# SW6106_A_C_LED.net
KiCad netlist of a schematic drawn in Altium Designer
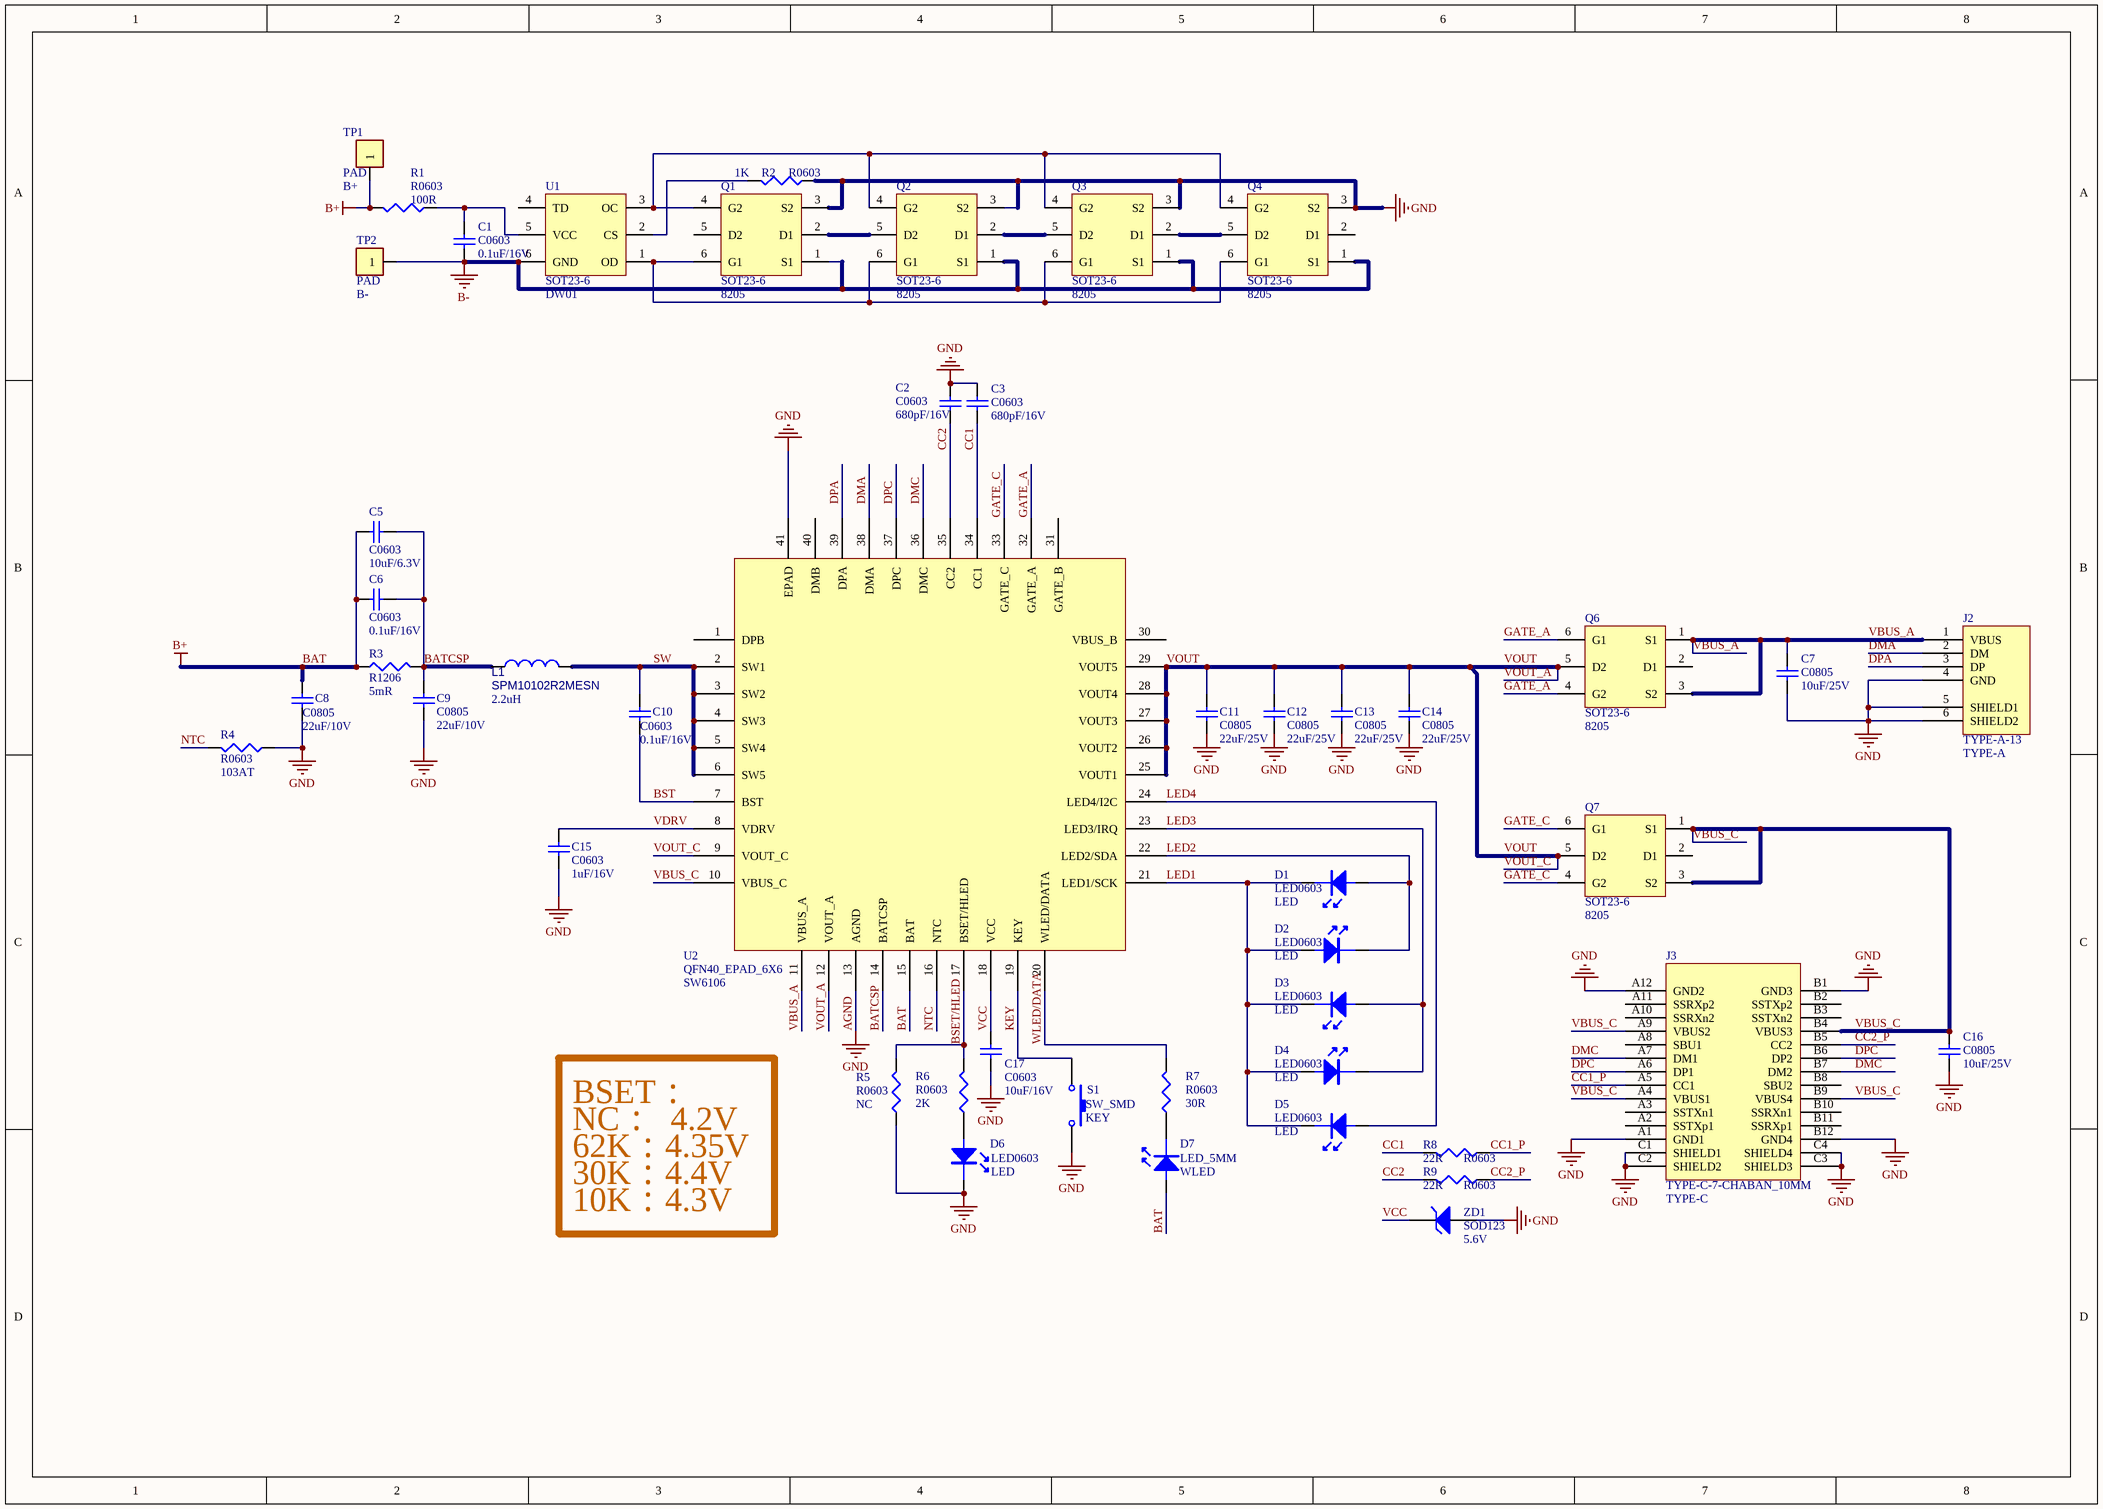
[diagram p0: SW6106+A+C+LED.SchDoc]

(export (version "E")
  (design (tool "Eeschema 10.0.6"))
  (components
    (comp (ref "C1")
      (value "C0603")
      (footprint "C0603")
      (description "Capacitor")
      (fields (field (name "ALTIUM_VALUE") "0.1uF/16V") (field (name "PUBLISHER") "Altium Limited"))
      (libsource (lib "*") (part "Cap"))
    )
    (comp (ref "C2")
      (value "C0603")
      (footprint "C0603")
      (description "Capacitor")
      (fields (field (name "ALTIUM_VALUE") "680pF/16V") (field (name "PUBLISHER") "Altium Limited"))
      (libsource (lib "*") (part "CAP0603"))
    )
    (comp (ref "C3")
      (value "C0603")
      (footprint "C0603")
      (description "Capacitor")
      (fields (field (name "ALTIUM_VALUE") "680pF/16V") (field (name "PUBLISHER") "Altium Limited"))
      (libsource (lib "*") (part "CAP0603"))
    )
    (comp (ref "C5")
      (value "C0603")
      (footprint "C0603")
      (description "Capacitor")
      (fields (field (name "ALTIUM_VALUE") "10uF/6.3V") (field (name "PUBLISHER") "Altium Limited"))
      (libsource (lib "*") (part "CAP0603"))
    )
    (comp (ref "C6")
      (value "C0603")
      (footprint "C0603")
      (description "Capacitor")
      (fields (field (name "ALTIUM_VALUE") "0.1uF/16V") (field (name "PUBLISHER") "Altium Limited"))
      (libsource (lib "*") (part "CAP0603"))
    )
    (comp (ref "C7")
      (value "C0805")
      (footprint "C0805")
      (description "Capacitor")
      (fields (field (name "ALTIUM_VALUE") "10uF/25V") (field (name "PUBLISHER") "Altium Limited"))
      (libsource (lib "*") (part "CAP0603"))
    )
    (comp (ref "C8")
      (value "C0805")
      (footprint "C0805")
      (description "Capacitor")
      (fields (field (name "ALTIUM_VALUE") "22uF/10V") (field (name "PUBLISHER") "Altium Limited"))
      (libsource (lib "*") (part "CAP0805"))
    )
    (comp (ref "C9")
      (value "C0805")
      (footprint "C0805")
      (description "Capacitor")
      (fields (field (name "ALTIUM_VALUE") "22uF/10V") (field (name "PUBLISHER") "Altium Limited"))
      (libsource (lib "*") (part "CAP0805"))
    )
    (comp (ref "C10")
      (value "C0603")
      (footprint "C0603")
      (description "Capacitor")
      (fields (field (name "ALTIUM_VALUE") "0.1uF/16V") (field (name "PUBLISHER") "Altium Limited"))
      (libsource (lib "*") (part "CAP0603"))
    )
    (comp (ref "C11")
      (value "C0805")
      (footprint "C0805")
      (description "Capacitor")
      (fields (field (name "ALTIUM_VALUE") "22uF/25V") (field (name "PUBLISHER") "Altium Limited"))
      (libsource (lib "*") (part "CAP0805"))
    )
    (comp (ref "C12")
      (value "C0805")
      (footprint "C0805")
      (description "Capacitor")
      (fields (field (name "ALTIUM_VALUE") "22uF/25V") (field (name "PUBLISHER") "Altium Limited"))
      (libsource (lib "*") (part "CAP0805"))
    )
    (comp (ref "C13")
      (value "C0805")
      (footprint "C0805")
      (description "Capacitor")
      (fields (field (name "ALTIUM_VALUE") "22uF/25V") (field (name "PUBLISHER") "Altium Limited"))
      (libsource (lib "*") (part "CAP0805"))
    )
    (comp (ref "C14")
      (value "C0805")
      (footprint "C0805")
      (description "Capacitor")
      (fields (field (name "ALTIUM_VALUE") "22uF/25V") (field (name "PUBLISHER") "Altium Limited"))
      (libsource (lib "*") (part "CAP0805"))
    )
    (comp (ref "C15")
      (value "C0603")
      (footprint "C0603")
      (description "Capacitor")
      (fields (field (name "ALTIUM_VALUE") "1uF/16V") (field (name "PUBLISHER") "Altium Limited"))
      (libsource (lib "*") (part "CAP0603"))
    )
    (comp (ref "C16")
      (value "C0805")
      (footprint "C0805")
      (description "Capacitor")
      (fields (field (name "ALTIUM_VALUE") "10uF/25V") (field (name "PUBLISHER") "Altium Limited"))
      (libsource (lib "*") (part "CAP0603"))
    )
    (comp (ref "C17")
      (value "C0603")
      (footprint "C0603")
      (description "Capacitor")
      (fields (field (name "ALTIUM_VALUE") "10uF/16V") (field (name "PUBLISHER") "Altium Limited"))
      (libsource (lib "*") (part "CAP0603"))
    )
    (comp (ref "D1") (value "LED") (footprint "LED0603") (libsource (lib "*") (part "LED")))
    (comp (ref "D2") (value "LED") (footprint "LED0603") (libsource (lib "*") (part "LED")))
    (comp (ref "D3") (value "LED") (footprint "LED0603") (libsource (lib "*") (part "LED")))
    (comp (ref "D4") (value "LED") (footprint "LED0603") (libsource (lib "*") (part "LED")))
    (comp (ref "D5") (value "LED") (footprint "LED0603") (libsource (lib "*") (part "LED")))
    (comp (ref "D6") (value "LED") (footprint "LED0603") (libsource (lib "*") (part "LED")))
    (comp (ref "D7")
      (value "WLED")
      (footprint "LED_5MM")
      (fields (field (name "FOOTPRINF") "LED_5MM") (field (name "Comment") "LED_5MM"))
      (libsource (lib "*") (part "LED"))
    )
    (comp (ref "J2")
      (value "TYPE-A")
      (footprint "TYPE-A-13")
      (fields (field (name "FOOTPRINF") "TYPE-A-13") (field (name "Comment") "TYPE-A-1"))
      (libsource (lib "*") (part "TYPE-A-1"))
    )
    (comp (ref "J3")
      (value "TYPE-C")
      (footprint "TYPE-C-7-CHABAN_10MM")
      (libsource (lib "*") (part "TYPE-C"))
    )
    (comp (ref "L1")
      (value "SPM10102R2MESN")
      (footprint "INDUCTOR_SPM1010")
      (fields (field (name "ALTIUM_VALUE") "2.2uH"))
      (libsource (lib "*") (part "INDUCTOR"))
    )
    (comp (ref "Q1")
      (value "8205")
      (footprint "SOT23-6")
      (fields (field (name "FOOTPRINF") "SOT23-6"))
      (libsource (lib "") (part "8205B_1"))
    )
    (comp (ref "Q2")
      (value "8205")
      (footprint "SOT23-6")
      (fields (field (name "FOOTPRINF") "SOT23-6"))
      (libsource (lib "") (part "8205B_1"))
    )
    (comp (ref "Q3")
      (value "8205")
      (footprint "SOT23-6")
      (fields (field (name "FOOTPRINF") "SOT23-6"))
      (libsource (lib "") (part "8205B_1"))
    )
    (comp (ref "Q4")
      (value "8205")
      (footprint "SOT23-6")
      (fields (field (name "FOOTPRINF") "SOT23-6"))
      (libsource (lib "") (part "8205B_1"))
    )
    (comp (ref "Q6")
      (value "8205")
      (footprint "SOT23-6")
      (fields (field (name "FOOTPRINF") "SOT23-6"))
      (libsource (lib "*") (part "8205B"))
    )
    (comp (ref "Q7")
      (value "8205")
      (footprint "SOT23-6")
      (fields (field (name "FOOTPRINF") "SOT23-6"))
      (libsource (lib "*") (part "8205B"))
    )
    (comp (ref "R1")
      (value "R0603")
      (footprint "R0603")
      (description "Resistor")
      (fields (field (name "ALTIUM_VALUE") "100R") (field (name "PUBLISHER") "Altium Limited"))
      (libsource (lib "*") (part "Res3"))
    )
    (comp (ref "R2")
      (value "R0603")
      (footprint "R0603")
      (description "Resistor")
      (fields (field (name "ALTIUM_VALUE") "1K") (field (name "PUBLISHER") "Altium Limited"))
      (libsource (lib "*") (part "Res3"))
    )
    (comp (ref "R3")
      (value "R1206")
      (footprint "R1206")
      (description "Resistor")
      (fields (field (name "ALTIUM_VALUE") "5mR") (field (name "PUBLISHER") "Altium Limited"))
      (libsource (lib "*") (part "RES"))
    )
    (comp (ref "R4")
      (value "R0603")
      (footprint "R0603")
      (description "Resistor")
      (fields (field (name "ALTIUM_VALUE") "103AT") (field (name "PUBLISHER") "Altium Limited"))
      (libsource (lib "*") (part "RES"))
    )
    (comp (ref "R5")
      (value "R0603")
      (footprint "R0603")
      (description "Resistor")
      (fields (field (name "ALTIUM_VALUE") "NC") (field (name "PUBLISHER") "Altium Limited"))
      (libsource (lib "*") (part "RES"))
    )
    (comp (ref "R6")
      (value "R0603")
      (footprint "R0603")
      (description "Resistor")
      (fields (field (name "ALTIUM_VALUE") "2K") (field (name "PUBLISHER") "Altium Limited"))
      (libsource (lib "*") (part "RES"))
    )
    (comp (ref "R7")
      (value "R0603")
      (footprint "R0603")
      (description "Resistor")
      (fields (field (name "ALTIUM_VALUE") "30R") (field (name "PUBLISHER") "Altium Limited"))
      (libsource (lib "*") (part "RES"))
    )
    (comp (ref "R8")
      (value "R0603")
      (footprint "R0603")
      (description "Resistor")
      (fields (field (name "ALTIUM_VALUE") "22R") (field (name "PUBLISHER") "Altium Limited"))
      (libsource (lib "*") (part "RES"))
    )
    (comp (ref "R9")
      (value "R0603")
      (footprint "R0603")
      (description "Resistor")
      (fields (field (name "ALTIUM_VALUE") "22R") (field (name "PUBLISHER") "Altium Limited"))
      (libsource (lib "*") (part "RES"))
    )
    (comp (ref "S1")
      (value "KEY")
      (footprint "SW_SMD")
      (fields (field (name "FOOTPRINF") "SW_SMD"))
      (libsource (lib "*") (part "SW K"))
    )
    (comp (ref "TP1") (value "B+") (footprint "PAD") (libsource (lib "") (part "Test Point_1")))
    (comp (ref "TP2") (value "B-") (footprint "PAD") (libsource (lib "*") (part "Test Point")))
    (comp (ref "U1")
      (value "DW01")
      (footprint "SOT23-6")
      (fields (field (name "FOOTPRINF") "SOT23-6"))
      (libsource (lib "*") (part "DW01"))
    )
    (comp (ref "U2")
      (value "SW6106")
      (footprint "QFN40_EPAD_6X6")
      (libsource (lib "TEST") (part "SW6106_AFC"))
    )
    (comp (ref "ZD1")
      (value "SOD123")
      (footprint "SOD-123")
      (description "Zener Diode")
      (fields (field (name "ALTIUM_UNNAMED_1") "5.6V"))
      (libsource (lib "Miscellaneous Devices") (part "D Zener"))
    )
  )
  (nets
    (net (code "1") (name "/BATCSP") (class "Default")
      (node (ref "C5") (pin "2") (pinfunction "2_2") (pintype "passive"))
      (node (ref "C6") (pin "2") (pinfunction "2_2") (pintype "passive"))
      (node (ref "C9") (pin "2") (pinfunction "2_2") (pintype "passive"))
      (node (ref "L1") (pin "1") (pinfunction "1_1") (pintype "passive"))
      (node (ref "R3") (pin "2") (pinfunction "2_2") (pintype "passive"))
      (node (ref "U2") (pin "14") (pinfunction "BATCSP_14") (pintype "passive"))
    )
    (net (code "2") (name "/BSET{slash}HLED") (class "Default")
      (node (ref "R5") (pin "2") (pinfunction "2_2") (pintype "passive"))
      (node (ref "R6") (pin "2") (pinfunction "2_2") (pintype "passive"))
      (node (ref "U2") (pin "17") (pinfunction "BSET/HLED_17") (pintype "passive"))
    )
    (net (code "3") (name "/BST") (class "Default")
      (node (ref "C10") (pin "1") (pinfunction "1_1") (pintype "passive"))
      (node (ref "U2") (pin "7") (pinfunction "BST_7") (pintype "passive"))
    )
    (net (code "4") (name "/CC1") (class "Default")
      (node (ref "C3") (pin "1") (pinfunction "1_1") (pintype "passive"))
      (node (ref "R8") (pin "2") (pinfunction "2_2") (pintype "passive"))
      (node (ref "U2") (pin "34") (pinfunction "CC1_34") (pintype "passive"))
    )
    (net (code "5") (name "/CC1_P") (class "Default")
      (node (ref "J3") (pin "A5") (pinfunction "CC1_A5") (pintype "passive"))
      (node (ref "R8") (pin "1") (pinfunction "1_1") (pintype "passive"))
    )
    (net (code "6") (name "/CC2") (class "Default")
      (node (ref "C2") (pin "1") (pinfunction "1_1") (pintype "passive"))
      (node (ref "R9") (pin "2") (pinfunction "2_2") (pintype "passive"))
      (node (ref "U2") (pin "35") (pinfunction "CC2_35") (pintype "passive"))
    )
    (net (code "7") (name "/CC2_P") (class "Default")
      (node (ref "J3") (pin "B5") (pinfunction "CC2_B5") (pintype "passive"))
      (node (ref "R9") (pin "1") (pinfunction "1_1") (pintype "passive"))
    )
    (net (code "8") (name "/DMA") (class "Default")
      (node (ref "J2") (pin "2") (pinfunction "DM_2") (pintype "passive"))
      (node (ref "U2") (pin "38") (pinfunction "DMA_38") (pintype "passive"))
    )
    (net (code "9") (name "/DMC") (class "Default")
      (node (ref "J3") (pin "A7") (pinfunction "DM1_A7") (pintype "passive"))
      (node (ref "J3") (pin "B7") (pinfunction "DM2_B7") (pintype "passive"))
      (node (ref "U2") (pin "36") (pinfunction "DMC_36") (pintype "passive"))
    )
    (net (code "10") (name "/DPA") (class "Default")
      (node (ref "J2") (pin "3") (pinfunction "DP_3") (pintype "passive"))
      (node (ref "U2") (pin "39") (pinfunction "DPA_39") (pintype "passive"))
    )
    (net (code "11") (name "/DPC") (class "Default")
      (node (ref "J3") (pin "A6") (pinfunction "DP1_A6") (pintype "passive"))
      (node (ref "J3") (pin "B6") (pinfunction "DP2_B6") (pintype "passive"))
      (node (ref "U2") (pin "37") (pinfunction "DPC_37") (pintype "passive"))
    )
    (net (code "12") (name "/GATE_A") (class "Default")
      (node (ref "Q6") (pin "4") (pinfunction "G2_4") (pintype "passive"))
      (node (ref "Q6") (pin "6") (pinfunction "G1_6") (pintype "passive"))
      (node (ref "U2") (pin "32") (pinfunction "GATE_A_32") (pintype "passive"))
    )
    (net (code "13") (name "/GATE_C") (class "Default")
      (node (ref "Q7") (pin "4") (pinfunction "G2_4") (pintype "passive"))
      (node (ref "Q7") (pin "6") (pinfunction "G1_6") (pintype "passive"))
      (node (ref "U2") (pin "33") (pinfunction "GATE_C_33") (pintype "passive"))
    )
    (net (code "14") (name "/KEY") (class "Default")
      (node (ref "S1") (pin "1") (pinfunction "1_1") (pintype "passive"))
      (node (ref "U2") (pin "19") (pinfunction "KEY_19") (pintype "passive"))
    )
    (net (code "15") (name "/LED1") (class "Default")
      (node (ref "D1") (pin "2") (pinfunction "K_2") (pintype "passive"))
      (node (ref "D2") (pin "1") (pinfunction "A_1") (pintype "passive"))
      (node (ref "D3") (pin "2") (pinfunction "K_2") (pintype "passive"))
      (node (ref "D4") (pin "1") (pinfunction "A_1") (pintype "passive"))
      (node (ref "D5") (pin "2") (pinfunction "K_2") (pintype "passive"))
      (node (ref "U2") (pin "21") (pinfunction "LED1/SCK_21") (pintype "passive"))
    )
    (net (code "16") (name "/LED2") (class "Default")
      (node (ref "D1") (pin "1") (pinfunction "A_1") (pintype "passive"))
      (node (ref "D2") (pin "2") (pinfunction "K_2") (pintype "passive"))
      (node (ref "U2") (pin "22") (pinfunction "LED2/SDA_22") (pintype "passive"))
    )
    (net (code "17") (name "/LED3") (class "Default")
      (node (ref "D3") (pin "1") (pinfunction "A_1") (pintype "passive"))
      (node (ref "D4") (pin "2") (pinfunction "K_2") (pintype "passive"))
      (node (ref "U2") (pin "23") (pinfunction "LED3/IRQ_23") (pintype "passive"))
    )
    (net (code "18") (name "/LED4") (class "Default")
      (node (ref "D5") (pin "1") (pinfunction "A_1") (pintype "passive"))
      (node (ref "U2") (pin "24") (pinfunction "LED4/I2C_24") (pintype "passive"))
    )
    (net (code "19") (name "/NTC") (class "Default")
      (node (ref "R4") (pin "2") (pinfunction "2_2") (pintype "passive"))
      (node (ref "U2") (pin "16") (pinfunction "NTC_16") (pintype "passive"))
    )
    (net (code "20") (name "/SW") (class "Default")
      (node (ref "C10") (pin "2") (pinfunction "2_2") (pintype "passive"))
      (node (ref "L1") (pin "2") (pinfunction "2_2") (pintype "passive"))
      (node (ref "U2") (pin "2") (pinfunction "SW1_2") (pintype "passive"))
      (node (ref "U2") (pin "3") (pinfunction "SW2_3") (pintype "passive"))
      (node (ref "U2") (pin "4") (pinfunction "SW3_4") (pintype "passive"))
      (node (ref "U2") (pin "5") (pinfunction "SW4_5") (pintype "passive"))
      (node (ref "U2") (pin "6") (pinfunction "SW5_6") (pintype "passive"))
    )
    (net (code "21") (name "/VBUS_A") (class "Default")
      (node (ref "C7") (pin "2") (pinfunction "2_2") (pintype "passive"))
      (node (ref "J2") (pin "1") (pinfunction "VBUS_1") (pintype "passive"))
      (node (ref "Q6") (pin "1") (pinfunction "S1_1") (pintype "passive"))
      (node (ref "Q6") (pin "3") (pinfunction "S2_3") (pintype "passive"))
      (node (ref "U2") (pin "11") (pinfunction "VBUS_A_11") (pintype "passive"))
    )
    (net (code "22") (name "/VBUS_C") (class "Default")
      (node (ref "C16") (pin "2") (pinfunction "2_2") (pintype "passive"))
      (node (ref "J3") (pin "A4") (pinfunction "VBUS1_A4") (pintype "passive"))
      (node (ref "J3") (pin "A9") (pinfunction "VBUS2_A9") (pintype "passive"))
      (node (ref "J3") (pin "B4") (pinfunction "VBUS3_B4") (pintype "passive"))
      (node (ref "J3") (pin "B9") (pinfunction "VBUS4_B9") (pintype "passive"))
      (node (ref "Q7") (pin "1") (pinfunction "S1_1") (pintype "passive"))
      (node (ref "Q7") (pin "3") (pinfunction "S2_3") (pintype "passive"))
      (node (ref "U2") (pin "10") (pinfunction "VBUS_C_10") (pintype "passive"))
    )
    (net (code "23") (name "/VCC") (class "Default")
      (node (ref "C17") (pin "2") (pinfunction "2_2") (pintype "passive"))
      (node (ref "U2") (pin "18") (pinfunction "VCC_18") (pintype "passive"))
      (node (ref "ZD1") (pin "2") (pinfunction "K_2") (pintype "passive"))
    )
    (net (code "24") (name "/VDRV") (class "Default")
      (node (ref "C15") (pin "2") (pinfunction "2_2") (pintype "passive"))
      (node (ref "U2") (pin "8") (pinfunction "VDRV_8") (pintype "passive"))
    )
    (net (code "25") (name "/VOUT") (class "Default")
      (node (ref "C11") (pin "2") (pinfunction "2_2") (pintype "passive"))
      (node (ref "C12") (pin "2") (pinfunction "2_2") (pintype "passive"))
      (node (ref "C13") (pin "2") (pinfunction "2_2") (pintype "passive"))
      (node (ref "C14") (pin "2") (pinfunction "2_2") (pintype "passive"))
      (node (ref "Q6") (pin "5") (pinfunction "D2_5") (pintype "passive"))
      (node (ref "Q7") (pin "5") (pinfunction "D2_5") (pintype "passive"))
      (node (ref "U2") (pin "12") (pinfunction "VOUT_A_12") (pintype "passive"))
      (node (ref "U2") (pin "25") (pinfunction "VOUT1_25") (pintype "passive"))
      (node (ref "U2") (pin "26") (pinfunction "VOUT2_26") (pintype "passive"))
      (node (ref "U2") (pin "27") (pinfunction "VOUT3_27") (pintype "passive"))
      (node (ref "U2") (pin "28") (pinfunction "VOUT4_28") (pintype "passive"))
      (node (ref "U2") (pin "29") (pinfunction "VOUT5_29") (pintype "passive"))
      (node (ref "U2") (pin "9") (pinfunction "VOUT_C_9") (pintype "passive"))
    )
    (net (code "26") (name "/WLED{slash}DATA") (class "Default")
      (node (ref "R7") (pin "2") (pinfunction "2_2") (pintype "passive"))
      (node (ref "U2") (pin "20") (pinfunction "WLED/DATA_20") (pintype "passive"))
    )
    (net (code "27") (name "B+") (class "Default")
      (node (ref "C5") (pin "1") (pinfunction "1_1") (pintype "passive"))
      (node (ref "C6") (pin "1") (pinfunction "1_1") (pintype "passive"))
      (node (ref "C8") (pin "2") (pinfunction "2_2") (pintype "passive"))
      (node (ref "D7") (pin "1") (pinfunction "A_1") (pintype "passive"))
      (node (ref "R1") (pin "2") (pinfunction "2_2") (pintype "passive"))
      (node (ref "R3") (pin "1") (pinfunction "1_1") (pintype "passive"))
      (node (ref "TP1") (pin "1") (pinfunction "1_1") (pintype "passive"))
      (node (ref "U2") (pin "15") (pinfunction "BAT_15") (pintype "passive"))
    )
    (net (code "28") (name "B-") (class "Default")
      (node (ref "C1") (pin "1") (pinfunction "1_1") (pintype "passive"))
      (node (ref "Q1") (pin "1") (pinfunction "S1_1") (pintype "passive"))
      (node (ref "Q2") (pin "1") (pinfunction "S1_1") (pintype "passive"))
      (node (ref "Q3") (pin "1") (pinfunction "S1_1") (pintype "passive"))
      (node (ref "Q4") (pin "1") (pinfunction "S1_1") (pintype "passive"))
      (node (ref "TP2") (pin "1") (pinfunction "1_1") (pintype "passive"))
      (node (ref "U1") (pin "6") (pinfunction "GND_6") (pintype "passive"))
    )
    (net (code "29") (name "GND") (class "Default")
      (node (ref "C11") (pin "1") (pinfunction "1_1") (pintype "passive"))
      (node (ref "C12") (pin "1") (pinfunction "1_1") (pintype "passive"))
      (node (ref "C13") (pin "1") (pinfunction "1_1") (pintype "passive"))
      (node (ref "C14") (pin "1") (pinfunction "1_1") (pintype "passive"))
      (node (ref "C15") (pin "1") (pinfunction "1_1") (pintype "passive"))
      (node (ref "C16") (pin "1") (pinfunction "1_1") (pintype "passive"))
      (node (ref "C17") (pin "1") (pinfunction "1_1") (pintype "passive"))
      (node (ref "C2") (pin "2") (pinfunction "2_2") (pintype "passive"))
      (node (ref "C3") (pin "2") (pinfunction "2_2") (pintype "passive"))
      (node (ref "C7") (pin "1") (pinfunction "1_1") (pintype "passive"))
      (node (ref "C8") (pin "1") (pinfunction "1_1") (pintype "passive"))
      (node (ref "C9") (pin "1") (pinfunction "1_1") (pintype "passive"))
      (node (ref "D6") (pin "2") (pinfunction "K_2") (pintype "passive"))
      (node (ref "J2") (pin "4") (pinfunction "GND_4") (pintype "passive"))
      (node (ref "J2") (pin "5") (pinfunction "SHIELD1_5") (pintype "passive"))
      (node (ref "J2") (pin "6") (pinfunction "SHIELD2_6") (pintype "passive"))
      (node (ref "J3") (pin "A1") (pinfunction "GND1_A1") (pintype "passive"))
      (node (ref "J3") (pin "A12") (pinfunction "GND2_A12") (pintype "passive"))
      (node (ref "J3") (pin "B1") (pinfunction "GND3_B1") (pintype "passive"))
      (node (ref "J3") (pin "B12") (pinfunction "GND4_B12") (pintype "passive"))
      (node (ref "J3") (pin "C1") (pinfunction "SHIELD1_C1") (pintype "passive"))
      (node (ref "J3") (pin "C2") (pinfunction "SHIELD2_C2") (pintype "passive"))
      (node (ref "J3") (pin "C3") (pinfunction "SHIELD3_C3") (pintype "passive"))
      (node (ref "J3") (pin "C4") (pinfunction "SHIELD4_C4") (pintype "passive"))
      (node (ref "Q1") (pin "3") (pinfunction "S2_3") (pintype "passive"))
      (node (ref "Q2") (pin "3") (pinfunction "S2_3") (pintype "passive"))
      (node (ref "Q3") (pin "3") (pinfunction "S2_3") (pintype "passive"))
      (node (ref "Q4") (pin "3") (pinfunction "S2_3") (pintype "passive"))
      (node (ref "R2") (pin "1") (pinfunction "1_1") (pintype "passive"))
      (node (ref "R4") (pin "1") (pinfunction "1_1") (pintype "passive"))
      (node (ref "R5") (pin "1") (pinfunction "1_1") (pintype "passive"))
      (node (ref "S1") (pin "2") (pinfunction "2_2") (pintype "passive"))
      (node (ref "U2") (pin "13") (pinfunction "AGND_13") (pintype "passive"))
      (node (ref "U2") (pin "41") (pinfunction "EPAD_41") (pintype "passive"))
      (node (ref "ZD1") (pin "1") (pinfunction "A_1") (pintype "passive"))
    )
    (net (code "30") (name "Net-(D6-A)") (class "Default")
      (node (ref "D6") (pin "1") (pinfunction "A_1") (pintype "passive"))
      (node (ref "R6") (pin "1") (pinfunction "1_1") (pintype "passive"))
    )
    (net (code "31") (name "Net-(D7-K)") (class "Default")
      (node (ref "D7") (pin "2") (pinfunction "K_2") (pintype "passive"))
      (node (ref "R7") (pin "1") (pinfunction "1_1") (pintype "passive"))
    )
    (net (code "32") (name "Net-(Q1-D1)") (class "Default")
      (node (ref "Q1") (pin "2") (pinfunction "D1_2") (pintype "passive"))
      (node (ref "Q2") (pin "5") (pinfunction "D2_5") (pintype "passive"))
    )
    (net (code "33") (name "Net-(Q1-G1)") (class "Default")
      (node (ref "Q1") (pin "6") (pinfunction "G1_6") (pintype "passive"))
      (node (ref "Q2") (pin "6") (pinfunction "G1_6") (pintype "passive"))
      (node (ref "Q3") (pin "6") (pinfunction "G1_6") (pintype "passive"))
      (node (ref "Q4") (pin "6") (pinfunction "G1_6") (pintype "passive"))
      (node (ref "U1") (pin "1") (pinfunction "OD_1") (pintype "passive"))
    )
    (net (code "34") (name "Net-(Q1-G2)") (class "Default")
      (node (ref "Q1") (pin "4") (pinfunction "G2_4") (pintype "passive"))
      (node (ref "Q2") (pin "4") (pinfunction "G2_4") (pintype "passive"))
      (node (ref "Q3") (pin "4") (pinfunction "G2_4") (pintype "passive"))
      (node (ref "Q4") (pin "4") (pinfunction "G2_4") (pintype "passive"))
      (node (ref "U1") (pin "3") (pinfunction "OC_3") (pintype "passive"))
    )
    (net (code "35") (name "Net-(Q2-D1)") (class "Default")
      (node (ref "Q2") (pin "2") (pinfunction "D1_2") (pintype "passive"))
      (node (ref "Q3") (pin "5") (pinfunction "D2_5") (pintype "passive"))
    )
    (net (code "36") (name "Net-(Q3-D1)") (class "Default")
      (node (ref "Q3") (pin "2") (pinfunction "D1_2") (pintype "passive"))
      (node (ref "Q4") (pin "5") (pinfunction "D2_5") (pintype "passive"))
    )
    (net (code "37") (name "Net-(U1-CS)") (class "Default")
      (node (ref "R2") (pin "2") (pinfunction "2_2") (pintype "passive"))
      (node (ref "U1") (pin "2") (pinfunction "CS_2") (pintype "passive"))
    )
    (net (code "38") (name "Net-(U1-VCC)") (class "Default")
      (node (ref "C1") (pin "2") (pinfunction "2_2") (pintype "passive"))
      (node (ref "R1") (pin "1") (pinfunction "1_1") (pintype "passive"))
      (node (ref "U1") (pin "5") (pinfunction "VCC_5") (pintype "passive"))
    )
    (net (code "39") (name "unconnected-(J3-SBU1-PadA8)") (class "Default")
      (node (ref "J3") (pin "A8") (pinfunction "SBU1_A8") (pintype "passive"))
    )
    (net (code "40") (name "unconnected-(J3-SBU2-PadB8)") (class "Default")
      (node (ref "J3") (pin "B8") (pinfunction "SBU2_B8") (pintype "passive"))
    )
    (net (code "41") (name "unconnected-(J3-SSRXn1-PadB10)") (class "Default")
      (node (ref "J3") (pin "B10") (pinfunction "SSRXn1_B10") (pintype "passive"))
    )
    (net (code "42") (name "unconnected-(J3-SSRXn2-PadA10)") (class "Default")
      (node (ref "J3") (pin "A10") (pinfunction "SSRXn2_A10") (pintype "passive"))
    )
    (net (code "43") (name "unconnected-(J3-SSRXp1-PadB11)") (class "Default")
      (node (ref "J3") (pin "B11") (pinfunction "SSRXp1_B11") (pintype "passive"))
    )
    (net (code "44") (name "unconnected-(J3-SSRXp2-PadA11)") (class "Default")
      (node (ref "J3") (pin "A11") (pinfunction "SSRXp2_A11") (pintype "passive"))
    )
    (net (code "45") (name "unconnected-(J3-SSTXn1-PadA3)") (class "Default")
      (node (ref "J3") (pin "A3") (pinfunction "SSTXn1_A3") (pintype "passive"))
    )
    (net (code "46") (name "unconnected-(J3-SSTXn2-PadB3)") (class "Default")
      (node (ref "J3") (pin "B3") (pinfunction "SSTXn2_B3") (pintype "passive"))
    )
    (net (code "47") (name "unconnected-(J3-SSTXp1-PadA2)") (class "Default")
      (node (ref "J3") (pin "A2") (pinfunction "SSTXp1_A2") (pintype "passive"))
    )
    (net (code "48") (name "unconnected-(J3-SSTXp2-PadB2)") (class "Default")
      (node (ref "J3") (pin "B2") (pinfunction "SSTXp2_B2") (pintype "passive"))
    )
    (net (code "49") (name "unconnected-(Q1-D2-Pad5)") (class "Default")
      (node (ref "Q1") (pin "5") (pinfunction "D2_5") (pintype "passive"))
    )
    (net (code "50") (name "unconnected-(Q4-D1-Pad2)") (class "Default")
      (node (ref "Q4") (pin "2") (pinfunction "D1_2") (pintype "passive"))
    )
    (net (code "51") (name "unconnected-(Q6-D1-Pad2)") (class "Default")
      (node (ref "Q6") (pin "2") (pinfunction "D1_2") (pintype "passive"))
    )
    (net (code "52") (name "unconnected-(Q7-D1-Pad2)") (class "Default")
      (node (ref "Q7") (pin "2") (pinfunction "D1_2") (pintype "passive"))
    )
    (net (code "53") (name "unconnected-(U1-TD-Pad4)") (class "Default")
      (node (ref "U1") (pin "4") (pinfunction "TD_4") (pintype "passive"))
    )
    (net (code "54") (name "unconnected-(U2-DMB-Pad40)") (class "Default")
      (node (ref "U2") (pin "40") (pinfunction "DMB_40") (pintype "passive"))
    )
    (net (code "55") (name "unconnected-(U2-DPB-Pad1)") (class "Default")
      (node (ref "U2") (pin "1") (pinfunction "DPB_1") (pintype "passive"))
    )
    (net (code "56") (name "unconnected-(U2-GATE_B-Pad31)") (class "Default")
      (node (ref "U2") (pin "31") (pinfunction "GATE_B_31") (pintype "passive"))
    )
    (net (code "57") (name "unconnected-(U2-VBUS_B-Pad30)") (class "Default")
      (node (ref "U2") (pin "30") (pinfunction "VBUS_B_30") (pintype "passive"))
    )
  )
)
